# pi_sainsmart_relay_4.net
KiCad netlist of a schematic drawn in EAGLE
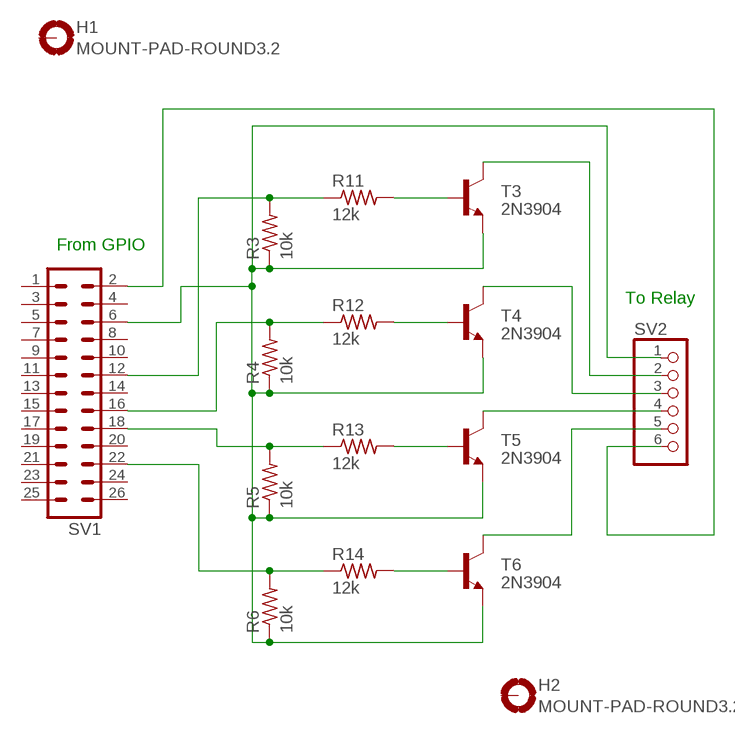
[diagram p0: schematic, sheet 1]

(export (version "E")
  (design (tool "Eeschema 10.0.6"))
  (components
    (comp (ref "H1")
      (value "MOUNT-PAD-ROUND3.2")
      (footprint "eagle-import:3,2-PAD")
      (libsource (lib "eagle-import") (part "MOUNT-PAD-ROUND3.2"))
    )
    (comp (ref "H2")
      (value "MOUNT-PAD-ROUND3.2")
      (footprint "eagle-import:3,2-PAD")
      (libsource (lib "eagle-import") (part "MOUNT-PAD-ROUND3.2"))
    )
    (comp (ref "R3")
      (value "10k")
      (footprint "eagle-import:0204V")
      (libsource (lib "eagle-import") (part "R-US_0204/2V"))
    )
    (comp (ref "R4")
      (value "10k")
      (footprint "eagle-import:0204V")
      (libsource (lib "eagle-import") (part "R-US_0204/2V"))
    )
    (comp (ref "R5")
      (value "10k")
      (footprint "eagle-import:0204V")
      (libsource (lib "eagle-import") (part "R-US_0204/2V"))
    )
    (comp (ref "R6")
      (value "10k")
      (footprint "eagle-import:0204V")
      (libsource (lib "eagle-import") (part "R-US_0204/2V"))
    )
    (comp (ref "R11")
      (value "12k")
      (footprint "eagle-import:0207_12")
      (libsource (lib "eagle-import") (part "R-US_0207/12"))
    )
    (comp (ref "R12")
      (value "12k")
      (footprint "eagle-import:0207_12")
      (libsource (lib "eagle-import") (part "R-US_0207/12"))
    )
    (comp (ref "R13")
      (value "12k")
      (footprint "eagle-import:0207_12")
      (libsource (lib "eagle-import") (part "R-US_0207/12"))
    )
    (comp (ref "R14")
      (value "12k")
      (footprint "eagle-import:0207_12")
      (libsource (lib "eagle-import") (part "R-US_0207/12"))
    )
    (comp (ref "SV1")
      (value "MA13-2")
      (footprint "eagle-import:MA13-2")
      (libsource (lib "eagle-import") (part "MA13-2"))
    )
    (comp (ref "SV2")
      (value "PINHD-1X6")
      (footprint "eagle-import:1X06")
      (libsource (lib "eagle-import") (part "PINHD-1X6"))
    )
    (comp (ref "T3")
      (value "2N3904")
      (footprint "eagle-import:TO92-EBC")
      (libsource (lib "eagle-import") (part "-NPN-TO92-EBC"))
    )
    (comp (ref "T4")
      (value "2N3904")
      (footprint "eagle-import:TO92-EBC")
      (libsource (lib "eagle-import") (part "-NPN-TO92-EBC"))
    )
    (comp (ref "T5")
      (value "2N3904")
      (footprint "eagle-import:TO92-EBC")
      (libsource (lib "eagle-import") (part "-NPN-TO92-EBC"))
    )
    (comp (ref "T6")
      (value "2N3904")
      (footprint "eagle-import:TO92-EBC")
      (libsource (lib "eagle-import") (part "-NPN-TO92-EBC"))
    )
  )
  (nets
    (net (code "1") (name "Net-(R3-Pad1)") (class "Default")
      (node (ref "R3") (pin "1") (pinfunction "1_1") (pintype "passive"))
      (node (ref "R4") (pin "1") (pinfunction "1_1") (pintype "passive"))
      (node (ref "R5") (pin "1") (pinfunction "1_1") (pintype "passive"))
      (node (ref "R6") (pin "1") (pinfunction "1_1") (pintype "passive"))
      (node (ref "SV1") (pin "6") (pinfunction "6_6") (pintype "passive"))
      (node (ref "SV2") (pin "1") (pinfunction "1_1") (pintype "passive"))
      (node (ref "T3") (pin "E") (pinfunction "E_E") (pintype "passive"))
      (node (ref "T4") (pin "E") (pinfunction "E_E") (pintype "passive"))
      (node (ref "T5") (pin "E") (pinfunction "E_E") (pintype "passive"))
      (node (ref "T6") (pin "E") (pinfunction "E_E") (pintype "passive"))
    )
    (net (code "2") (name "Net-(R11-Pad1)") (class "Default")
      (node (ref "R11") (pin "1") (pinfunction "1_1") (pintype "passive"))
      (node (ref "R3") (pin "2") (pinfunction "2_2") (pintype "passive"))
      (node (ref "SV1") (pin "12") (pinfunction "12_12") (pintype "passive"))
    )
    (net (code "3") (name "Net-(R11-Pad2)") (class "Default")
      (node (ref "R11") (pin "2") (pinfunction "2_2") (pintype "passive"))
      (node (ref "T3") (pin "B") (pinfunction "B_B") (pintype "passive"))
    )
    (net (code "4") (name "Net-(R12-Pad1)") (class "Default")
      (node (ref "R12") (pin "1") (pinfunction "1_1") (pintype "passive"))
      (node (ref "R4") (pin "2") (pinfunction "2_2") (pintype "passive"))
      (node (ref "SV1") (pin "16") (pinfunction "16_16") (pintype "passive"))
    )
    (net (code "5") (name "Net-(R12-Pad2)") (class "Default")
      (node (ref "R12") (pin "2") (pinfunction "2_2") (pintype "passive"))
      (node (ref "T4") (pin "B") (pinfunction "B_B") (pintype "passive"))
    )
    (net (code "6") (name "Net-(R13-Pad1)") (class "Default")
      (node (ref "R13") (pin "1") (pinfunction "1_1") (pintype "passive"))
      (node (ref "R5") (pin "2") (pinfunction "2_2") (pintype "passive"))
      (node (ref "SV1") (pin "18") (pinfunction "18_18") (pintype "passive"))
    )
    (net (code "7") (name "Net-(R13-Pad2)") (class "Default")
      (node (ref "R13") (pin "2") (pinfunction "2_2") (pintype "passive"))
      (node (ref "T5") (pin "B") (pinfunction "B_B") (pintype "passive"))
    )
    (net (code "8") (name "Net-(R14-Pad1)") (class "Default")
      (node (ref "R14") (pin "1") (pinfunction "1_1") (pintype "passive"))
      (node (ref "R6") (pin "2") (pinfunction "2_2") (pintype "passive"))
      (node (ref "SV1") (pin "22") (pinfunction "22_22") (pintype "passive"))
    )
    (net (code "9") (name "Net-(R14-Pad2)") (class "Default")
      (node (ref "R14") (pin "2") (pinfunction "2_2") (pintype "passive"))
      (node (ref "T6") (pin "B") (pinfunction "B_B") (pintype "passive"))
    )
    (net (code "10") (name "Net-(SV1-Pad2)") (class "Default")
      (node (ref "SV1") (pin "2") (pinfunction "2_2") (pintype "passive"))
      (node (ref "SV2") (pin "6") (pinfunction "6_6") (pintype "passive"))
    )
    (net (code "11") (name "Net-(SV2-Pad2)") (class "Default")
      (node (ref "SV2") (pin "2") (pinfunction "2_2") (pintype "passive"))
      (node (ref "T3") (pin "C") (pinfunction "C_C") (pintype "passive"))
    )
    (net (code "12") (name "Net-(SV2-Pad3)") (class "Default")
      (node (ref "SV2") (pin "3") (pinfunction "3_3") (pintype "passive"))
      (node (ref "T4") (pin "C") (pinfunction "C_C") (pintype "passive"))
    )
    (net (code "13") (name "Net-(SV2-Pad4)") (class "Default")
      (node (ref "SV2") (pin "4") (pinfunction "4_4") (pintype "passive"))
      (node (ref "T5") (pin "C") (pinfunction "C_C") (pintype "passive"))
    )
    (net (code "14") (name "Net-(SV2-Pad5)") (class "Default")
      (node (ref "SV2") (pin "5") (pinfunction "5_5") (pintype "passive"))
      (node (ref "T6") (pin "C") (pinfunction "C_C") (pintype "passive"))
    )
    (net (code "15") (name "unconnected-(H1-MOUNT-PadB3,2)") (class "Default")
      (node (ref "H1") (pin "B3,2") (pinfunction "MOUNT_B3,2") (pintype "passive"))
    )
    (net (code "16") (name "unconnected-(H2-MOUNT-PadB3,2)") (class "Default")
      (node (ref "H2") (pin "B3,2") (pinfunction "MOUNT_B3,2") (pintype "passive"))
    )
    (net (code "17") (name "unconnected-(SV1-Pad1)") (class "Default")
      (node (ref "SV1") (pin "1") (pinfunction "1_1") (pintype "passive"))
    )
    (net (code "18") (name "unconnected-(SV1-Pad3)") (class "Default")
      (node (ref "SV1") (pin "3") (pinfunction "3_3") (pintype "passive"))
    )
    (net (code "19") (name "unconnected-(SV1-Pad4)") (class "Default")
      (node (ref "SV1") (pin "4") (pinfunction "4_4") (pintype "passive"))
    )
    (net (code "20") (name "unconnected-(SV1-Pad5)") (class "Default")
      (node (ref "SV1") (pin "5") (pinfunction "5_5") (pintype "passive"))
    )
    (net (code "21") (name "unconnected-(SV1-Pad7)") (class "Default")
      (node (ref "SV1") (pin "7") (pinfunction "7_7") (pintype "passive"))
    )
    (net (code "22") (name "unconnected-(SV1-Pad8)") (class "Default")
      (node (ref "SV1") (pin "8") (pinfunction "8_8") (pintype "passive"))
    )
    (net (code "23") (name "unconnected-(SV1-Pad9)") (class "Default")
      (node (ref "SV1") (pin "9") (pinfunction "9_9") (pintype "passive"))
    )
    (net (code "24") (name "unconnected-(SV1-Pad10)") (class "Default")
      (node (ref "SV1") (pin "10") (pinfunction "10_10") (pintype "passive"))
    )
    (net (code "25") (name "unconnected-(SV1-Pad11)") (class "Default")
      (node (ref "SV1") (pin "11") (pinfunction "11_11") (pintype "passive"))
    )
    (net (code "26") (name "unconnected-(SV1-Pad13)") (class "Default")
      (node (ref "SV1") (pin "13") (pinfunction "13_13") (pintype "passive"))
    )
    (net (code "27") (name "unconnected-(SV1-Pad14)") (class "Default")
      (node (ref "SV1") (pin "14") (pinfunction "14_14") (pintype "passive"))
    )
    (net (code "28") (name "unconnected-(SV1-Pad15)") (class "Default")
      (node (ref "SV1") (pin "15") (pinfunction "15_15") (pintype "passive"))
    )
    (net (code "29") (name "unconnected-(SV1-Pad17)") (class "Default")
      (node (ref "SV1") (pin "17") (pinfunction "17_17") (pintype "passive"))
    )
    (net (code "30") (name "unconnected-(SV1-Pad19)") (class "Default")
      (node (ref "SV1") (pin "19") (pinfunction "19_19") (pintype "passive"))
    )
    (net (code "31") (name "unconnected-(SV1-Pad20)") (class "Default")
      (node (ref "SV1") (pin "20") (pinfunction "20_20") (pintype "passive"))
    )
    (net (code "32") (name "unconnected-(SV1-Pad21)") (class "Default")
      (node (ref "SV1") (pin "21") (pinfunction "21_21") (pintype "passive"))
    )
    (net (code "33") (name "unconnected-(SV1-Pad23)") (class "Default")
      (node (ref "SV1") (pin "23") (pinfunction "23_23") (pintype "passive"))
    )
    (net (code "34") (name "unconnected-(SV1-Pad24)") (class "Default")
      (node (ref "SV1") (pin "24") (pinfunction "24_24") (pintype "passive"))
    )
    (net (code "35") (name "unconnected-(SV1-Pad25)") (class "Default")
      (node (ref "SV1") (pin "25") (pinfunction "25_25") (pintype "passive"))
    )
    (net (code "36") (name "unconnected-(SV1-Pad26)") (class "Default")
      (node (ref "SV1") (pin "26") (pinfunction "26_26") (pintype "passive"))
    )
  )
)
